# POWER.net
KiCad netlist of a schematic drawn in Altium Designer
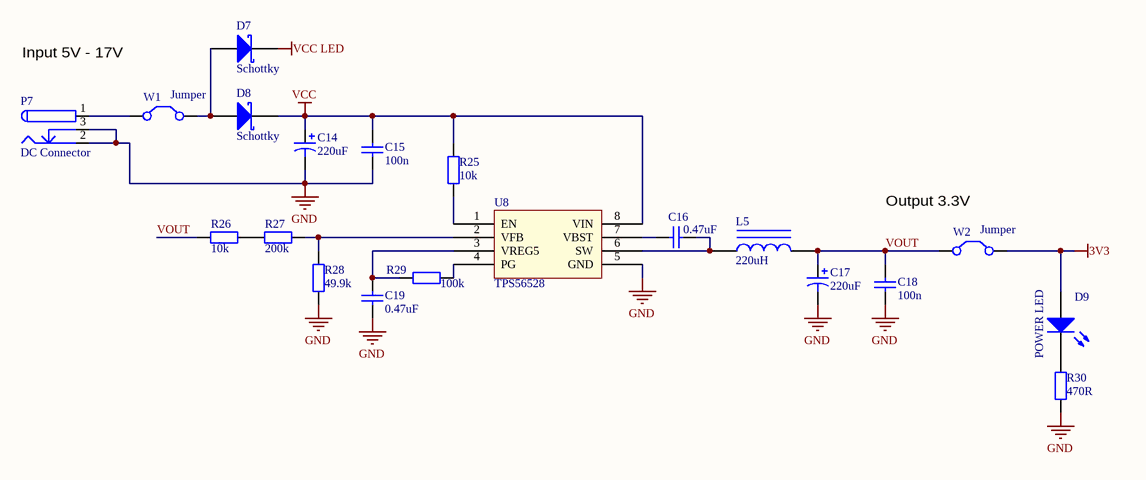
[diagram p0: POWER.SchDoc]

(export (version "E")
  (design (tool "Eeschema 10.0.6"))
  (components
    (comp (ref "C14")
      (value "220uF")
      (footprint "SMD CAPACITOR 220uF")
      (description "Capacitor")
      (fields (field (name "PUBLISHER") "Altium Limited"))
      (libsource (lib "Miscellaneous Devices") (part "Cap Pol1"))
    )
    (comp (ref "C15")
      (value "100n")
      (footprint "1608[0603]")
      (description "Capacitor")
      (fields (field (name "PUBLISHER") "Altium Limited"))
      (libsource (lib "Miscellaneous Devices") (part "Cap"))
    )
    (comp (ref "C16")
      (value "0.47uF")
      (footprint "1608[0603]")
      (description "Capacitor")
      (fields (field (name "PUBLISHER") "Altium Limited"))
      (libsource (lib "Miscellaneous Devices") (part "Cap"))
    )
    (comp (ref "C17")
      (value "220uF")
      (footprint "SMD CAPACITOR 220uF")
      (description "Capacitor")
      (fields (field (name "PUBLISHER") "Altium Limited"))
      (libsource (lib "Miscellaneous Devices") (part "Cap Pol1"))
    )
    (comp (ref "C18")
      (value "100n")
      (footprint "1608[0603]")
      (description "Capacitor")
      (fields (field (name "PUBLISHER") "Altium Limited"))
      (libsource (lib "Miscellaneous Devices") (part "Cap"))
    )
    (comp (ref "C19")
      (value "0.47uF")
      (footprint "1608[0603]")
      (description "Capacitor")
      (fields (field (name "PUBLISHER") "Altium Limited"))
      (libsource (lib "Miscellaneous Devices") (part "Cap"))
    )
    (comp (ref "D7")
      (value "Schottky")
      (footprint "SMB")
      (description "Schottky Diode")
      (fields (field (name "PUBLISHER") "Altium Limited"))
      (libsource (lib "Miscellaneous Devices") (part "D Schottky"))
    )
    (comp (ref "D8")
      (value "Schottky")
      (footprint "SMB")
      (description "Schottky Diode")
      (fields (field (name "PUBLISHER") "Altium Limited"))
      (libsource (lib "Miscellaneous Devices") (part "D Schottky"))
    )
    (comp (ref "D9")
      (value "POWER LED")
      (footprint "LED-1")
      (description "Typical INFRARED GaAs LED")
      (fields (field (name "PUBLISHER") "Altium Limited"))
      (libsource (lib "Miscellaneous Devices") (part "LED0"))
    )
    (comp (ref "L5")
      (value "220uH")
      (footprint "Inductor")
      (description "Magnetic-Core Inductor")
      (fields (field (name "PUBLISHER") "Altium Limited"))
      (libsource (lib "Miscellaneous Devices") (part "Inductor Iron"))
    )
    (comp (ref "P7")
      (value "DC Connector")
      (footprint "DC Connector")
      (description "DC Power Connector")
      (libsource (lib "LukaLIBRARY") (part "DC Connector"))
    )
    (comp (ref "R25")
      (value "10k")
      (footprint "1608[0603]")
      (description "Resistor")
      (fields (field (name "PUBLISHER") "Altium Limited"))
      (libsource (lib "Miscellaneous Devices") (part "Res2"))
    )
    (comp (ref "R26")
      (value "10k")
      (footprint "6-0805_L")
      (description "Resistor")
      (fields (field (name "PUBLISHER") "Altium Limited"))
      (libsource (lib "") (part "Res2_1"))
    )
    (comp (ref "R27")
      (value "200k")
      (footprint "6-0805_L")
      (description "Resistor")
      (fields (field (name "PUBLISHER") "Altium Limited"))
      (libsource (lib "") (part "Res2_1"))
    )
    (comp (ref "R28")
      (value "49.9k")
      (footprint "1608[0603]")
      (description "Resistor")
      (fields (field (name "PUBLISHER") "Altium Limited"))
      (libsource (lib "Miscellaneous Devices") (part "Res2"))
    )
    (comp (ref "R29")
      (value "100k")
      (footprint "1608[0603]")
      (description "Resistor")
      (fields (field (name "PUBLISHER") "Altium Limited"))
      (libsource (lib "") (part "Res2_1"))
    )
    (comp (ref "R30")
      (value "470R")
      (footprint "1608[0603]")
      (description "Resistor")
      (fields (field (name "PUBLISHER") "Altium Limited"))
      (libsource (lib "Miscellaneous Devices") (part "Res2"))
    )
    (comp (ref "U8")
      (value "TPS56528")
      (footprint "TPS56528")
      (description "Step-Down Converter 5A 4.5V-18V")
      (libsource (lib "LP_Lib") (part "TPS56528"))
    )
    (comp (ref "W1")
      (value "Jumper")
      (footprint "HDR1X2")
      (description "Jumper Wire")
      (fields (field (name "PUBLISHER") "Altium Limited"))
      (libsource (lib "Miscellaneous Devices") (part "Jumper"))
    )
    (comp (ref "W2")
      (value "Jumper")
      (footprint "HDR1X2")
      (description "Jumper Wire")
      (fields (field (name "PUBLISHER") "Altium Limited"))
      (libsource (lib "Miscellaneous Devices") (part "Jumper"))
    )
  )
  (nets
    (net (code "1") (name "/VOUT") (class "Default")
      (node (ref "C17") (pin "1") (pinfunction "1_1") (pintype "passive"))
      (node (ref "C18") (pin "1") (pinfunction "1_1") (pintype "passive"))
      (node (ref "L5") (pin "2") (pinfunction "2_2") (pintype "passive"))
      (node (ref "R26") (pin "2") (pinfunction "2_2") (pintype "passive"))
      (node (ref "W2") (pin "1") (pinfunction "C1_1") (pintype "passive"))
    )
    (net (code "2") (name "3V3") (class "Default")
      (node (ref "D9") (pin "1") (pinfunction "A_1") (pintype "passive"))
      (node (ref "W2") (pin "2") (pinfunction "C2_2") (pintype "passive"))
    )
    (net (code "3") (name "GND") (class "Default")
      (node (ref "C14") (pin "2") (pinfunction "2_2") (pintype "passive"))
      (node (ref "C15") (pin "2") (pinfunction "2_2") (pintype "passive"))
      (node (ref "C17") (pin "2") (pinfunction "2_2") (pintype "passive"))
      (node (ref "C18") (pin "2") (pinfunction "2_2") (pintype "passive"))
      (node (ref "C19") (pin "2") (pinfunction "2_2") (pintype "passive"))
      (node (ref "P7") (pin "2") (pinfunction "2_2") (pintype "power_in"))
      (node (ref "P7") (pin "3") (pinfunction "3_3") (pintype "power_in"))
      (node (ref "R28") (pin "1") (pinfunction "1_1") (pintype "passive"))
      (node (ref "R30") (pin "1") (pinfunction "1_1") (pintype "passive"))
      (node (ref "U8") (pin "5") (pinfunction "GND_5") (pintype "passive"))
    )
    (net (code "4") (name "Net-(D7-A)") (class "Default")
      (node (ref "D7") (pin "1") (pinfunction "A_1") (pintype "passive"))
      (node (ref "D8") (pin "1") (pinfunction "A_1") (pintype "passive"))
      (node (ref "W1") (pin "2") (pinfunction "C2_2") (pintype "passive"))
    )
    (net (code "5") (name "Net-(D9-K)") (class "Default")
      (node (ref "D9") (pin "2") (pinfunction "K_2") (pintype "passive"))
      (node (ref "R30") (pin "2") (pinfunction "2_2") (pintype "passive"))
    )
    (net (code "6") (name "Net-(R26-Pad1)") (class "Default")
      (node (ref "R26") (pin "1") (pinfunction "1_1") (pintype "passive"))
      (node (ref "R27") (pin "2") (pinfunction "2_2") (pintype "passive"))
    )
    (net (code "7") (name "Net-(U8-EN)") (class "Default")
      (node (ref "R25") (pin "1") (pinfunction "1_1") (pintype "passive"))
      (node (ref "U8") (pin "1") (pinfunction "EN_1") (pintype "passive"))
    )
    (net (code "8") (name "Net-(U8-PG)") (class "Default")
      (node (ref "R29") (pin "1") (pinfunction "1_1") (pintype "passive"))
      (node (ref "U8") (pin "4") (pinfunction "PG_4") (pintype "passive"))
    )
    (net (code "9") (name "Net-(U8-SW)") (class "Default")
      (node (ref "C16") (pin "2") (pinfunction "2_2") (pintype "passive"))
      (node (ref "L5") (pin "1") (pinfunction "1_1") (pintype "passive"))
      (node (ref "U8") (pin "6") (pinfunction "SW_6") (pintype "passive"))
    )
    (net (code "10") (name "Net-(U8-VBST)") (class "Default")
      (node (ref "C16") (pin "1") (pinfunction "1_1") (pintype "passive"))
      (node (ref "U8") (pin "7") (pinfunction "VBST_7") (pintype "passive"))
    )
    (net (code "11") (name "Net-(U8-VFB)") (class "Default")
      (node (ref "R27") (pin "1") (pinfunction "1_1") (pintype "passive"))
      (node (ref "R28") (pin "2") (pinfunction "2_2") (pintype "passive"))
      (node (ref "U8") (pin "2") (pinfunction "VFB_2") (pintype "passive"))
    )
    (net (code "12") (name "Net-(U8-VREG5)") (class "Default")
      (node (ref "C19") (pin "1") (pinfunction "1_1") (pintype "passive"))
      (node (ref "R29") (pin "2") (pinfunction "2_2") (pintype "passive"))
      (node (ref "U8") (pin "3") (pinfunction "VREG5_3") (pintype "passive"))
    )
    (net (code "13") (name "Net-(W1-C1)") (class "Default")
      (node (ref "P7") (pin "1") (pinfunction "1_1") (pintype "power_in"))
      (node (ref "W1") (pin "1") (pinfunction "C1_1") (pintype "passive"))
    )
    (net (code "14") (name "VCC") (class "Default")
      (node (ref "C14") (pin "1") (pinfunction "1_1") (pintype "passive"))
      (node (ref "C15") (pin "1") (pinfunction "1_1") (pintype "passive"))
      (node (ref "D8") (pin "2") (pinfunction "K_2") (pintype "passive"))
      (node (ref "R25") (pin "2") (pinfunction "2_2") (pintype "passive"))
      (node (ref "U8") (pin "8") (pinfunction "VIN_8") (pintype "passive"))
    )
    (net (code "15") (name "VCC LED") (class "Default")
      (node (ref "D7") (pin "2") (pinfunction "K_2") (pintype "passive"))
    )
  )
)
